# Sensor_Package.net
KiCad netlist of a schematic drawn in Altium Designer
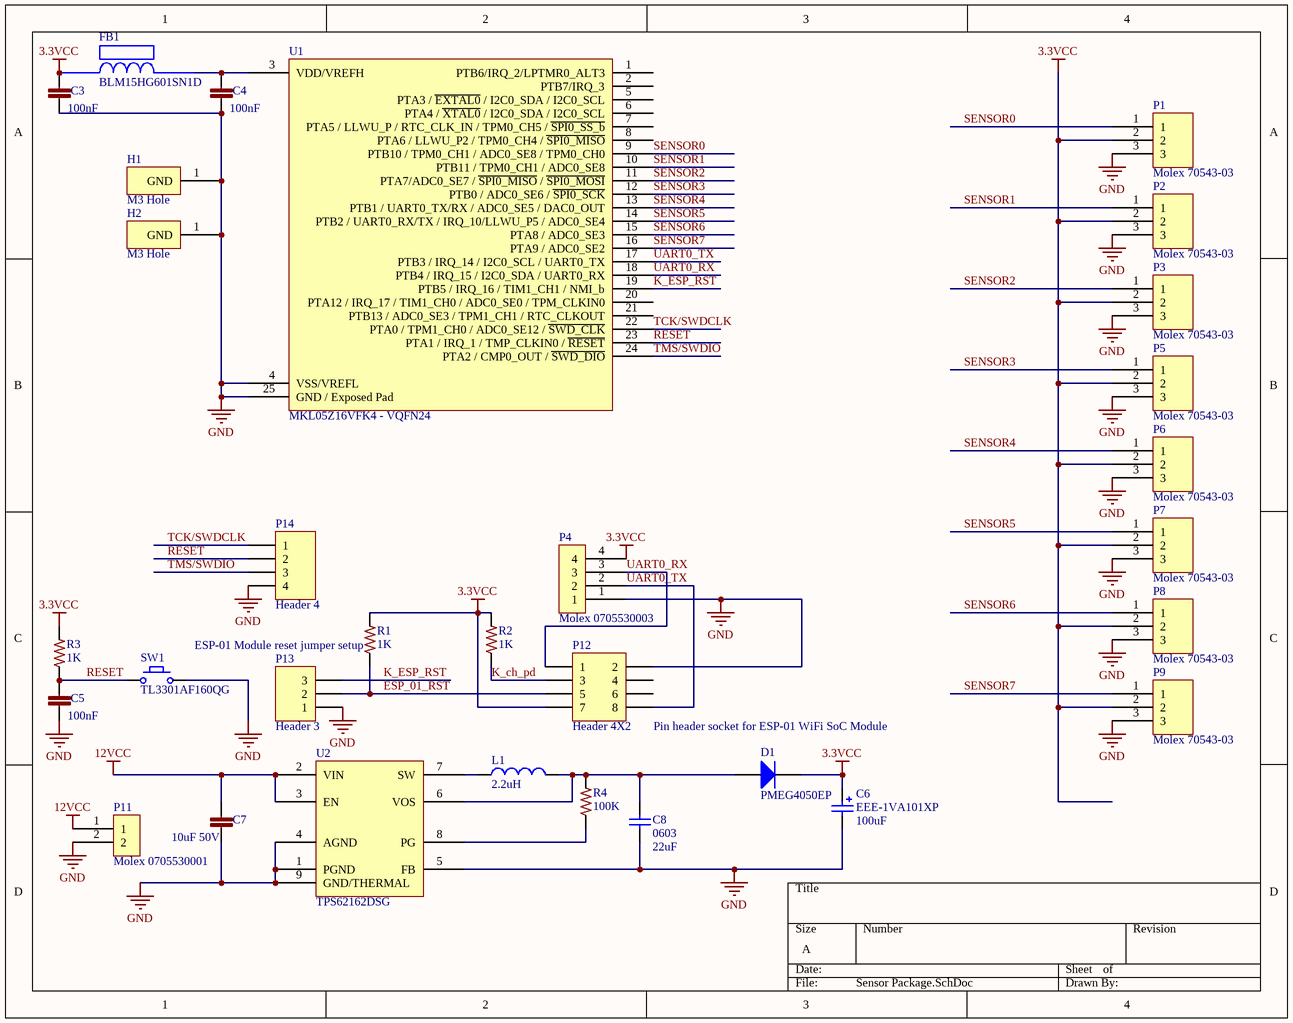
[diagram p0: Sensor Package.SchDoc]

(export (version "E")
  (design (tool "Eeschema 10.0.6"))
  (components
    (comp (ref "C3")
      (value "100nF")
      (footprint "C0402")
      (description "CAP CER 0402 100nF 16V 10% X7R")
      (fields
        (field (name "MANUFACTURERPARTNUMBER") "GRM155R71C104KA88D")
        (field (name "PUBLISHER") "UltiMachine")
      )
      (libsource (lib "3Delight") (part "GRM155R71C104KA88D"))
    )
    (comp (ref "C4")
      (value "100nF")
      (footprint "C0402")
      (description "CAP CER 0402 100nF 16V 10% X7R")
      (fields
        (field (name "MANUFACTURERPARTNUMBER") "GRM155R71C104KA88D")
        (field (name "PUBLISHER") "UltiMachine")
      )
      (libsource (lib "3Delight") (part "GRM155R71C104KA88D"))
    )
    (comp (ref "C5")
      (value "100nF")
      (footprint "C0402")
      (description "CAP CER 0402 100nF 16V 10% X7R")
      (fields
        (field (name "MANUFACTURERPARTNUMBER") "GRM155R71C104KA88D")
        (field (name "PUBLISHER") "UltiMachine")
      )
      (libsource (lib "3Delight") (part "GRM155R71C104KA88D"))
    )
    (comp (ref "C6")
      (value "EEE-1VA101XP")
      (footprint "EEE-1VA101XP")
      (description "CAP ALUM 100UF 35V 20% SMD")
      (fields (field (name "DIGIKEY PART #") "PCE3951CT-ND") (field (name "ALTIUM_VALUE") "100uF"))
      (libsource (lib "Tigershark3D") (part "EEE-1VA101XP"))
    )
    (comp (ref "C7")
      (value "10uF 50V")
      (footprint "C1206")
      (description "CAP CER 10UF 50V 10% X5R 1206")
      (fields
        (field (name "MANUFACTURER") "Samsung")
        (field (name "MANUFACTURERPARTNUMBER") "CL31A106KBHNNNE")
        (field (name "PUBLISHER") "UltiMachine")
      )
      (libsource (lib "Tigershark3D") (part "CL31A106KBHNNNE"))
    )
    (comp (ref "C8")
      (value "0603")
      (footprint "C0805")
      (description "CAP CER 22UF 6.3V 10% X5R 0805")
      (fields
        (field (name "MFR PART #") "CL21A226KQQNNNE")
        (field (name "MFR") "Samsung")
        (field (name "ALTIUM_VALUE") "22uF")
      )
      (libsource (lib "Sensor Package") (part "CL21A226KQQNNNE"))
    )
    (comp (ref "D1")
      (value "PMEG4050EP")
      (footprint "PMEG4050EP")
      (description "PMEG4050EP , Schottky Diode")
      (fields (field (name "PUBLISHER") "Altium Limited"))
      (libsource (lib "Sensor Package") (part "PMEG4050EP"))
    )
    (comp (ref "FB1")
      (value "BLM15HG601SN1D")
      (footprint "BLM18PG121SN1D")
      (libsource (lib "AHD Part Library") (part "BLM15HG601SN1D"))
    )
    (comp (ref "H1")
      (value "M3 Hole")
      (footprint "Hole-3mm")
      (description "3mm Hole")
      (libsource (lib "Sensor Package") (part "Hole"))
    )
    (comp (ref "H2")
      (value "M3 Hole")
      (footprint "Hole-3mm")
      (description "3mm Hole")
      (libsource (lib "Sensor Package") (part "Hole"))
    )
    (comp (ref "L1")
      (value "2.2uH")
      (footprint "VLS252012T-2R2M1R3")
      (description "VLS252012T-2R2M1R3")
      (fields (field (name "MFR") "TDK Corporation") (field (name "PUBLISHER") "Adam Vadala-Roth"))
      (libsource (lib "Sensor Package") (part "VLS252012T-2R2M1R3"))
    )
    (comp (ref "P1")
      (value "Molex 70543-03")
      (footprint "70543-03")
      (libsource (lib "RADMBo Schematic Library") (part "Molex Endstop"))
    )
    (comp (ref "P2")
      (value "Molex 70543-03")
      (footprint "70543-03")
      (libsource (lib "RADMBo Schematic Library") (part "Molex Endstop"))
    )
    (comp (ref "P3")
      (value "Molex 70543-03")
      (footprint "70543-03")
      (libsource (lib "RADMBo Schematic Library") (part "Molex Endstop"))
    )
    (comp (ref "P4")
      (value "Molex 0705530003")
      (footprint "0705530003")
      (description "Molex 0705530003 Right Angle 2.54mm Shrouded Header")
      (fields (field (name "MFR") "Molex"))
      (libsource (lib "Sensor Package") (part "0705530003"))
    )
    (comp (ref "P5")
      (value "Molex 70543-03")
      (footprint "70543-03")
      (libsource (lib "RADMBo Schematic Library") (part "Molex Endstop"))
    )
    (comp (ref "P6")
      (value "Molex 70543-03")
      (footprint "70543-03")
      (libsource (lib "RADMBo Schematic Library") (part "Molex Endstop"))
    )
    (comp (ref "P7")
      (value "Molex 70543-03")
      (footprint "70543-03")
      (libsource (lib "RADMBo Schematic Library") (part "Molex Endstop"))
    )
    (comp (ref "P8")
      (value "Molex 70543-03")
      (footprint "70543-03")
      (libsource (lib "RADMBo Schematic Library") (part "Molex Endstop"))
    )
    (comp (ref "P9")
      (value "Molex 70543-03")
      (footprint "70543-03")
      (libsource (lib "RADMBo Schematic Library") (part "Molex Endstop"))
    )
    (comp (ref "P11")
      (value "Molex 0705530001")
      (footprint "0705530001")
      (description "Molex 0705530002 Right Angle 2.54mm Shrouded Header")
      (fields (field (name "MFR") "Molex"))
      (libsource (lib "Sensor Package") (part "0705530001"))
    )
    (comp (ref "P12")
      (value "Header 4X2")
      (footprint "HDR2X4")
      (description "Header, 4-Pin, Dual row")
      (fields (field (name "PUBLISHER") "Altium Limited"))
      (libsource (lib "Miscellaneous Connectors") (part "Header 4X2"))
    )
    (comp (ref "P13")
      (value "Header 3")
      (footprint "HDR1X3")
      (description "Header, 3-Pin")
      (fields (field (name "PUBLISHER") "Altium Limited"))
      (libsource (lib "Miscellaneous Connectors") (part "Header 3"))
    )
    (comp (ref "P14")
      (value "Header 4")
      (footprint "HDR1X4")
      (description "Header, 4-Pin")
      (fields (field (name "PUBLISHER") "Altium Limited"))
      (libsource (lib "Miscellaneous Connectors") (part "Header 4"))
    )
    (comp (ref "R1")
      (value "1K")
      (footprint "R0603")
      (description "RES 0603 1K 100mW 1%")
      (fields
        (field (name "MANUFACTURERPARTNUMBER") "ERJ-3EKF1001V")
        (field (name "PUBLISHER") "UltiMachine")
      )
      (libsource (lib "3Delight") (part "ERJ-3EKF1001V"))
    )
    (comp (ref "R2")
      (value "1K")
      (footprint "R0603")
      (description "RES 0603 1K 100mW 1%")
      (fields
        (field (name "MANUFACTURERPARTNUMBER") "ERJ-3EKF1001V")
        (field (name "PUBLISHER") "UltiMachine")
      )
      (libsource (lib "3Delight") (part "ERJ-3EKF1001V"))
    )
    (comp (ref "R3")
      (value "1K")
      (footprint "R0603")
      (description "RES 0603 1K 100mW 1%")
      (fields
        (field (name "MANUFACTURERPARTNUMBER") "ERJ-3EKF1001V")
        (field (name "PUBLISHER") "UltiMachine")
      )
      (libsource (lib "3Delight") (part "ERJ-3EKF1001V"))
    )
    (comp (ref "R4")
      (value "100K")
      (footprint "R0603")
      (description "RES 100K OHM 1/10W 1% 0603 SMD")
      (fields
        (field (name "MANUFACTURERPARTNUMBER") "RC0603FR-07100KL")
        (field (name "PUBLISHER") "UltiMachine")
      )
      (libsource (lib "3Delight") (part "RC0603FR-07100KL"))
    )
    (comp (ref "SW1")
      (value "TL3301AF160QG")
      (footprint "TL3301AF160QG")
      (libsource (lib "MongoosMini") (part "TL3301AF160QG"))
    )
    (comp (ref "U1")
      (value "MKL05Z16VFK4 - VQFN24")
      (footprint "98ASA00474D")
      (description "ARM Cortex M0+")
      (libsource (lib "Encoder Fin") (part "MKL05Z16VFK4 - 24 Pin VQFN"))
    )
    (comp (ref "U2")
      (value "TPS62162DSG")
      (footprint "DSG8-1600X900TP")
      (libsource (lib "Adams Altium Library") (part "TPS62162SOP"))
    )
  )
  (nets
    (net (code "1") (name "/ESP_01_RST") (class "Default")
      (node (ref "P12") (pin "5") (pinfunction "5_5") (pintype "passive"))
      (node (ref "P13") (pin "2") (pinfunction "2_2") (pintype "passive"))
      (node (ref "R1") (pin "1") (pinfunction "1_1") (pintype "passive"))
    )
    (net (code "2") (name "/K_ESP_RST") (class "Default")
      (node (ref "P13") (pin "3") (pinfunction "3_3") (pintype "passive"))
      (node (ref "U1") (pin "19") (pinfunction "PTB5_/_IRQ_16_/_TIM1_CH1_/_NMI_b_19") (pintype "passive"))
    )
    (net (code "3") (name "/K_ch_pd") (class "Default")
      (node (ref "P12") (pin "3") (pinfunction "3_3") (pintype "passive"))
      (node (ref "R2") (pin "1") (pinfunction "1_1") (pintype "passive"))
    )
    (net (code "4") (name "/RESET") (class "Default")
      (node (ref "C5") (pin "1") (pinfunction "1_1") (pintype "passive"))
      (node (ref "P14") (pin "2") (pinfunction "2_2") (pintype "passive"))
      (node (ref "R3") (pin "1") (pinfunction "1_1") (pintype "passive"))
      (node (ref "SW1") (pin "1") (pintype "passive"))
      (node (ref "U1") (pin "23") (pinfunction "PTA1_/_IRQ_1_/_TMP_CLKIN0_/_~{RESET}_23") (pintype "passive"))
    )
    (net (code "5") (name "/SENSOR0") (class "Default")
      (node (ref "P1") (pin "1") (pinfunction "1_1") (pintype "passive"))
      (node (ref "U1") (pin "9") (pinfunction "PTB10_/_TPM0_CH1_/_ADC0_SE8_/_TPM0_CH0_9") (pintype "passive"))
    )
    (net (code "6") (name "/SENSOR1") (class "Default")
      (node (ref "P2") (pin "1") (pinfunction "1_1") (pintype "passive"))
      (node (ref "U1") (pin "10") (pinfunction "PTB11_/_TPM0_CH1_/_ADC0_SE8_10") (pintype "passive"))
    )
    (net (code "7") (name "/SENSOR2") (class "Default")
      (node (ref "P3") (pin "1") (pinfunction "1_1") (pintype "passive"))
      (node (ref "U1") (pin "11") (pinfunction "PTA7/ADC0_SE7_/_~{SPI0_MISO}_/_~{SPI0_MOSI}_11") (pintype "passive"))
    )
    (net (code "8") (name "/SENSOR3") (class "Default")
      (node (ref "P5") (pin "1") (pinfunction "1_1") (pintype "passive"))
      (node (ref "U1") (pin "12") (pinfunction "PTB0_/_ADC0_SE6_/_~{SPI0_SCK}_12") (pintype "passive"))
    )
    (net (code "9") (name "/SENSOR4") (class "Default")
      (node (ref "P6") (pin "1") (pinfunction "1_1") (pintype "passive"))
      (node (ref "U1") (pin "13") (pinfunction "PTB1_/_UART0_TX/RX_/_ADC0_SE5_/_DAC0_OUT_13") (pintype "passive"))
    )
    (net (code "10") (name "/SENSOR5") (class "Default")
      (node (ref "P7") (pin "1") (pinfunction "1_1") (pintype "passive"))
      (node (ref "U1") (pin "14") (pinfunction "PTB2_/_UART0_RX/TX_/_IRQ_10/LLWU_P5_/_ADC0_SE4_14") (pintype "passive"))
    )
    (net (code "11") (name "/SENSOR6") (class "Default")
      (node (ref "P8") (pin "1") (pinfunction "1_1") (pintype "passive"))
      (node (ref "U1") (pin "15") (pinfunction "PTA8_/_ADC0_SE3_15") (pintype "passive"))
    )
    (net (code "12") (name "/SENSOR7") (class "Default")
      (node (ref "P9") (pin "1") (pinfunction "1_1") (pintype "passive"))
      (node (ref "U1") (pin "16") (pinfunction "PTA9_/_ADC0_SE2_16") (pintype "passive"))
    )
    (net (code "13") (name "/TCK{slash}SWDCLK") (class "Default")
      (node (ref "P14") (pin "1") (pinfunction "1_1") (pintype "passive"))
      (node (ref "U1") (pin "22") (pinfunction "PTA0_/_TPM1_CH0_/_ADC0_SE12_/_~{SWD_CLK}_22") (pintype "passive"))
    )
    (net (code "14") (name "/TMS{slash}SWDIO") (class "Default")
      (node (ref "P14") (pin "3") (pinfunction "3_3") (pintype "passive"))
      (node (ref "U1") (pin "24") (pinfunction "PTA2_/_CMP0_OUT_/_~{SWD_DIO}_24") (pintype "passive"))
    )
    (net (code "15") (name "/UART0_RX") (class "Default")
      (node (ref "P12") (pin "1") (pinfunction "1_1") (pintype "passive"))
      (node (ref "P4") (pin "3") (pinfunction "3_3") (pintype "passive"))
      (node (ref "U1") (pin "18") (pinfunction "PTB4_/_IRQ_15_/_I2C0_SDA_/_UART0_RX_18") (pintype "passive"))
    )
    (net (code "16") (name "/UART0_TX") (class "Default")
      (node (ref "P12") (pin "8") (pinfunction "8_8") (pintype "passive"))
      (node (ref "P4") (pin "2") (pinfunction "2_2") (pintype "passive"))
      (node (ref "U1") (pin "17") (pinfunction "PTB3_/_IRQ_14_/_I2C0_SCL_/_UART0_TX_17") (pintype "passive"))
    )
    (net (code "17") (name "3.3VCC") (class "Default")
      (node (ref "C3") (pin "1") (pinfunction "1_1") (pintype "passive"))
      (node (ref "C6") (pin "1") (pinfunction "1_1") (pintype "passive"))
      (node (ref "D1") (pin "1") (pinfunction "A_1") (pintype "passive"))
      (node (ref "FB1") (pin "1") (pinfunction "1_1") (pintype "passive"))
      (node (ref "P1") (pin "2") (pinfunction "2_2") (pintype "passive"))
      (node (ref "P12") (pin "7") (pinfunction "7_7") (pintype "passive"))
      (node (ref "P2") (pin "2") (pinfunction "2_2") (pintype "passive"))
      (node (ref "P3") (pin "2") (pinfunction "2_2") (pintype "passive"))
      (node (ref "P4") (pin "4") (pinfunction "4_4") (pintype "passive"))
      (node (ref "P5") (pin "2") (pinfunction "2_2") (pintype "passive"))
      (node (ref "P6") (pin "2") (pinfunction "2_2") (pintype "passive"))
      (node (ref "P7") (pin "2") (pinfunction "2_2") (pintype "passive"))
      (node (ref "P8") (pin "2") (pinfunction "2_2") (pintype "passive"))
      (node (ref "P9") (pin "2") (pinfunction "2_2") (pintype "passive"))
      (node (ref "R1") (pin "2") (pinfunction "2_2") (pintype "passive"))
      (node (ref "R2") (pin "2") (pinfunction "2_2") (pintype "passive"))
      (node (ref "R3") (pin "2") (pinfunction "2_2") (pintype "passive"))
    )
    (net (code "18") (name "12VCC") (class "Default")
      (node (ref "C7") (pin "1") (pinfunction "1_1") (pintype "passive"))
      (node (ref "P11") (pin "1") (pinfunction "1_1") (pintype "passive"))
      (node (ref "U2") (pin "2") (pinfunction "VIN_2") (pintype "passive"))
      (node (ref "U2") (pin "3") (pinfunction "EN_3") (pintype "passive"))
    )
    (net (code "19") (name "GND") (class "Default")
      (node (ref "C3") (pin "2") (pinfunction "2_2") (pintype "passive"))
      (node (ref "C4") (pin "2") (pinfunction "2_2") (pintype "passive"))
      (node (ref "C5") (pin "2") (pinfunction "2_2") (pintype "passive"))
      (node (ref "C6") (pin "2") (pinfunction "2_2") (pintype "passive"))
      (node (ref "C7") (pin "2") (pinfunction "2_2") (pintype "passive"))
      (node (ref "C8") (pin "1") (pinfunction "1_1") (pintype "passive"))
      (node (ref "H1") (pin "1") (pinfunction "GND_1") (pintype "passive"))
      (node (ref "H2") (pin "1") (pinfunction "GND_1") (pintype "passive"))
      (node (ref "P1") (pin "3") (pinfunction "3_3") (pintype "passive"))
      (node (ref "P11") (pin "2") (pinfunction "2_2") (pintype "passive"))
      (node (ref "P12") (pin "2") (pinfunction "2_2") (pintype "passive"))
      (node (ref "P13") (pin "1") (pinfunction "1_1") (pintype "passive"))
      (node (ref "P14") (pin "4") (pinfunction "4_4") (pintype "passive"))
      (node (ref "P2") (pin "3") (pinfunction "3_3") (pintype "passive"))
      (node (ref "P3") (pin "3") (pinfunction "3_3") (pintype "passive"))
      (node (ref "P4") (pin "1") (pinfunction "1_1") (pintype "passive"))
      (node (ref "P5") (pin "3") (pinfunction "3_3") (pintype "passive"))
      (node (ref "P6") (pin "3") (pinfunction "3_3") (pintype "passive"))
      (node (ref "P7") (pin "3") (pinfunction "3_3") (pintype "passive"))
      (node (ref "P8") (pin "3") (pinfunction "3_3") (pintype "passive"))
      (node (ref "P9") (pin "3") (pinfunction "3_3") (pintype "passive"))
      (node (ref "SW1") (pin "2") (pintype "passive"))
      (node (ref "U1") (pin "25") (pinfunction "GND_/_Exposed_Pad_25") (pintype "passive"))
      (node (ref "U1") (pin "4") (pinfunction "VSS/VREFL_4") (pintype "passive"))
      (node (ref "U2") (pin "1") (pinfunction "PGND_1") (pintype "passive"))
      (node (ref "U2") (pin "4") (pinfunction "AGND_4") (pintype "passive"))
      (node (ref "U2") (pin "5") (pinfunction "FB_5") (pintype "passive"))
      (node (ref "U2") (pin "9") (pinfunction "GND/THERMAL_9") (pintype "passive"))
    )
    (net (code "20") (name "Net-(D1-K)") (class "Default")
      (node (ref "C8") (pin "2") (pinfunction "2_2") (pintype "passive"))
      (node (ref "D1") (pin "2") (pinfunction "K_2") (pintype "passive"))
      (node (ref "L1") (pin "2") (pinfunction "2_2") (pintype "passive"))
      (node (ref "R4") (pin "2") (pinfunction "2_2") (pintype "passive"))
      (node (ref "U2") (pin "6") (pinfunction "VOS_6") (pintype "passive"))
    )
    (net (code "21") (name "Net-(U1-VDD{slash}VREFH)") (class "Default")
      (node (ref "C4") (pin "1") (pinfunction "1_1") (pintype "passive"))
      (node (ref "FB1") (pin "2") (pinfunction "2_2") (pintype "passive"))
      (node (ref "U1") (pin "3") (pinfunction "VDD/VREFH_3") (pintype "passive"))
    )
    (net (code "22") (name "Net-(U2-PG)") (class "Default")
      (node (ref "R4") (pin "1") (pinfunction "1_1") (pintype "passive"))
      (node (ref "U2") (pin "8") (pinfunction "PG_8") (pintype "passive"))
    )
    (net (code "23") (name "Net-(U2-SW)") (class "Default")
      (node (ref "L1") (pin "1") (pinfunction "1_1") (pintype "passive"))
      (node (ref "U2") (pin "7") (pinfunction "SW_7") (pintype "passive"))
    )
    (net (code "24") (name "unconnected-(P12-Pad4)") (class "Default")
      (node (ref "P12") (pin "4") (pinfunction "4_4") (pintype "passive"))
    )
    (net (code "25") (name "unconnected-(P12-Pad6)") (class "Default")
      (node (ref "P12") (pin "6") (pinfunction "6_6") (pintype "passive"))
    )
    (net (code "26") (name "unconnected-(U1-PTA3_{slash}_~{EXTAL0}_{slash}_I2C0_SDA_{slash}_I2C0_SCL-Pad5)") (class "Default")
      (node (ref "U1") (pin "5") (pinfunction "PTA3_/_~{EXTAL0}_/_I2C0_SDA_/_I2C0_SCL_5") (pintype "passive"))
    )
    (net (code "27") (name "unconnected-(U1-PTA4_{slash}_~{XTAL0}_{slash}_I2C0_SDA_{slash}_I2C0_SCL-Pad6)") (class "Default")
      (node (ref "U1") (pin "6") (pinfunction "PTA4_/_~{XTAL0}_/_I2C0_SDA_/_I2C0_SCL_6") (pintype "passive"))
    )
    (net (code "28") (name "unconnected-(U1-PTA5_{slash}_LLWU_P_{slash}_RTC_CLK_IN_{slash}_TPM0_CH5_{slash}_~{SPI0_SS_b}-Pad7)") (class "Default")
      (node (ref "U1") (pin "7") (pinfunction "PTA5_/_LLWU_P_/_RTC_CLK_IN_/_TPM0_CH5_/_~{SPI0_SS_b}_7") (pintype "passive"))
    )
    (net (code "29") (name "unconnected-(U1-PTA6_{slash}_LLWU_P2_{slash}_TPM0_CH4_{slash}_~{SPI0_MISO}-Pad8)") (class "Default")
      (node (ref "U1") (pin "8") (pinfunction "PTA6_/_LLWU_P2_/_TPM0_CH4_/_~{SPI0_MISO}_8") (pintype "passive"))
    )
    (net (code "30") (name "unconnected-(U1-PTA12_{slash}_IRQ_17_{slash}_TIM1_CH0_{slash}_ADC0_SE0_{slash}_TPM_CLKIN0-Pad20)") (class "Default")
      (node (ref "U1") (pin "20") (pinfunction "PTA12_/_IRQ_17_/_TIM1_CH0_/_ADC0_SE0_/_TPM_CLKIN0_20") (pintype "passive"))
    )
    (net (code "31") (name "unconnected-(U1-PTB6{slash}IRQ_2{slash}LPTMR0_ALT3-Pad1)") (class "Default")
      (node (ref "U1") (pin "1") (pinfunction "PTB6/IRQ_2/LPTMR0_ALT3_1") (pintype "passive"))
    )
    (net (code "32") (name "unconnected-(U1-PTB7{slash}IRQ_3-Pad2)") (class "Default")
      (node (ref "U1") (pin "2") (pinfunction "PTB7/IRQ_3_2") (pintype "passive"))
    )
    (net (code "33") (name "unconnected-(U1-PTB13_{slash}_ADC0_SE3_{slash}_TPM1_CH1_{slash}_RTC_CLKOUT-Pad21)") (class "Default")
      (node (ref "U1") (pin "21") (pinfunction "PTB13_/_ADC0_SE3_/_TPM1_CH1_/_RTC_CLKOUT_21") (pintype "passive"))
    )
  )
)
